# main.net
KiCad netlist of a schematic drawn in Altium Designer
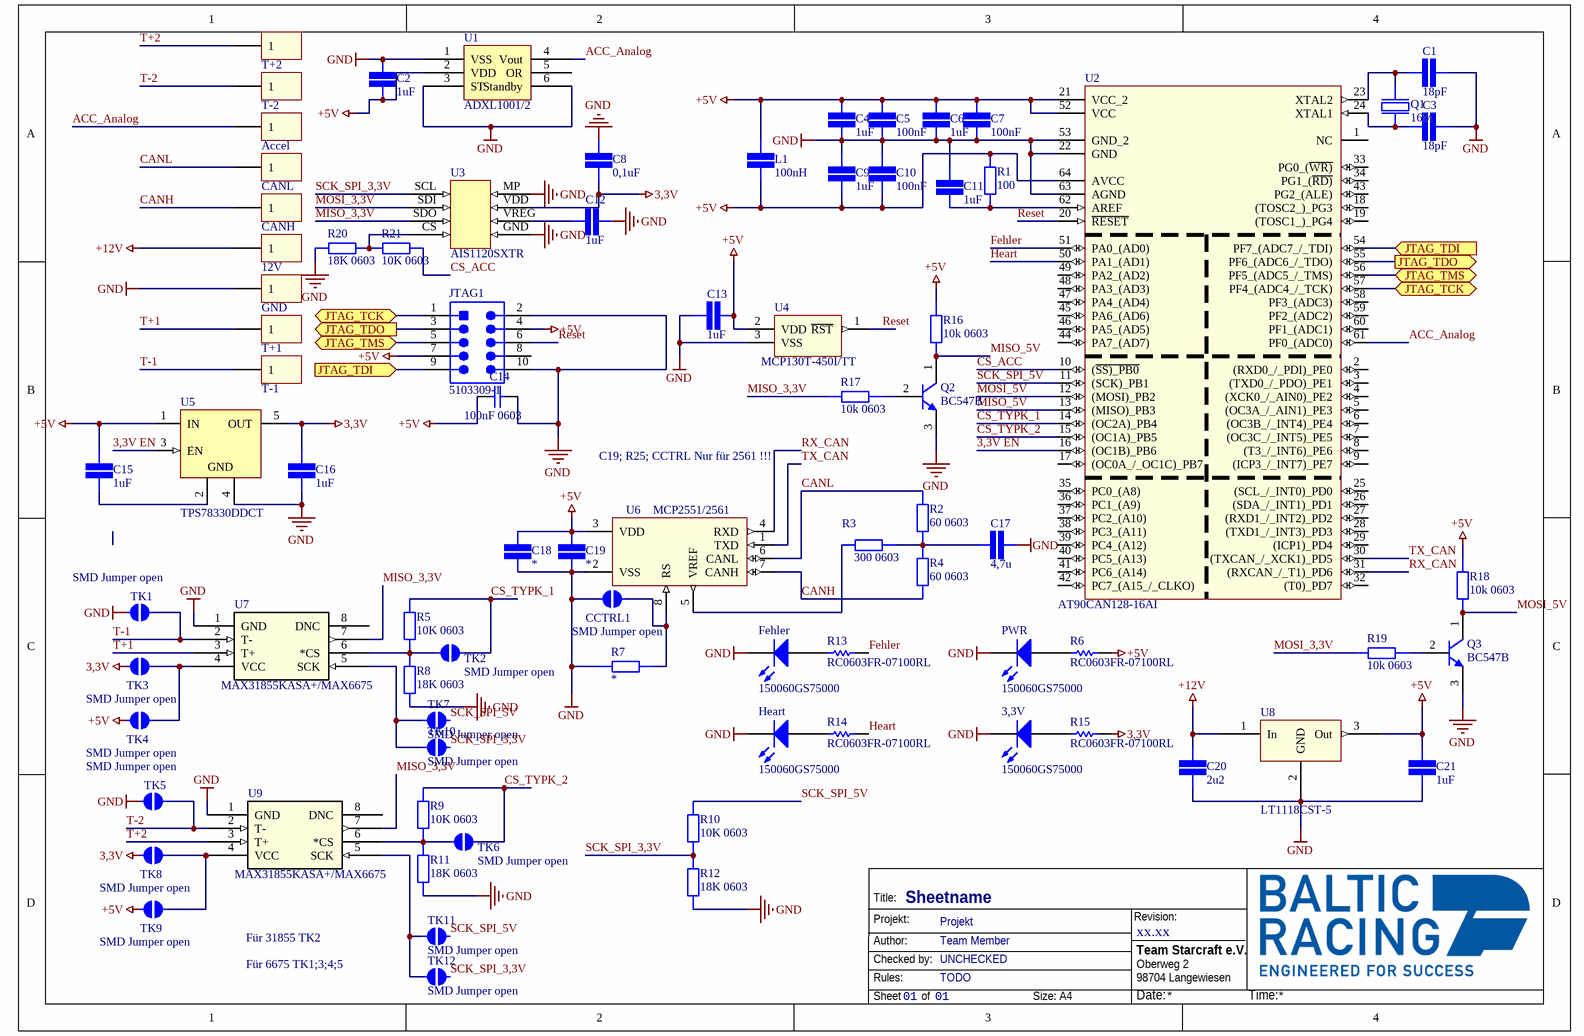
[diagram p0: main.SchDoc]

(export (version "E")
  (design (tool "Eeschema 10.0.6"))
  (components
    (comp (ref "3,3V")
      (value "150060GS75000")
      (footprint "0603_A")
      (description "SMD mono-color Chip LED, WL-SMCW, Green")
      (fields (field (name "MANUFACTURER") "Wuerth Elektronik"))
      (libsource (lib "Altium Content Vault") (part "WE-LED_K1A2-2"))
    )
    (comp (ref "12V")
      (value "61300111121")
      (footprint "61300111121")
      (description "WR-PHD 2.54 mm THT Pin Header, 1p")
      (fields (field (name "PUBLISHER") "Wurth Elektronik"))
      (libsource (lib "ALTIUM-PHD_2_54_THT_DUAL_PIN_HEADER_6130XX21121") (part "61300111121"))
    )
    (comp (ref "Accel")
      (value "61300111121")
      (footprint "61300111121")
      (description "WR-PHD 2.54 mm THT Pin Header, 1p")
      (fields (field (name "PUBLISHER") "Wurth Elektronik"))
      (libsource (lib "ALTIUM-PHD_2_54_THT_DUAL_PIN_HEADER_6130XX21121") (part "61300111121"))
    )
    (comp (ref "C1")
      (value "18pF")
      (footprint "CAP 0603/1608")
      (description "Capacitor with multiple Footprints")
      (fields (field (name "Comment") "SMD Capacitor"))
      (libsource (lib "Standardbauteile") (part "SMD Capacitor"))
    )
    (comp (ref "C2")
      (value "1uF")
      (footprint "CAP 0603/1608")
      (description "Capacitor with multiple Footprints")
      (fields (field (name "Comment") "SMD Capacitor"))
      (libsource (lib "") (part "SMD Capacitor_1"))
    )
    (comp (ref "C3")
      (value "18pF")
      (footprint "CAP 0603/1608")
      (description "Capacitor with multiple Footprints")
      (fields (field (name "Comment") "SMD Capacitor"))
      (libsource (lib "Standardbauteile") (part "SMD Capacitor"))
    )
    (comp (ref "C4")
      (value "1uF")
      (footprint "CAP 0603/1608")
      (description "Capacitor with multiple Footprints")
      (fields (field (name "Comment") "SMD Capacitor"))
      (libsource (lib "") (part "SMD Capacitor_1"))
    )
    (comp (ref "C5")
      (value "100nF")
      (footprint "CAP 0603/1608")
      (description "Capacitor with multiple Footprints")
      (fields (field (name "Comment") "SMD Capacitor"))
      (libsource (lib "") (part "SMD Capacitor_1"))
    )
    (comp (ref "C6")
      (value "1uF")
      (footprint "CAP 0603/1608")
      (description "Capacitor with multiple Footprints")
      (fields (field (name "Comment") "SMD Capacitor"))
      (libsource (lib "") (part "SMD Capacitor_1"))
    )
    (comp (ref "C7")
      (value "100nF")
      (footprint "CAP 0603/1608")
      (description "Capacitor with multiple Footprints")
      (fields (field (name "Comment") "SMD Capacitor"))
      (libsource (lib "") (part "SMD Capacitor_1"))
    )
    (comp (ref "C8")
      (value "0,1uF")
      (footprint "CAP 0603/1608")
      (description "Capacitor with multiple Footprints")
      (fields (field (name "Comment") "SMD Capacitor"))
      (libsource (lib "") (part "SMD Capacitor_1"))
    )
    (comp (ref "C9")
      (value "1uF")
      (footprint "CAP 0603/1608")
      (description "Capacitor with multiple Footprints")
      (fields (field (name "Comment") "SMD Capacitor"))
      (libsource (lib "") (part "SMD Capacitor_1"))
    )
    (comp (ref "C10")
      (value "100nF")
      (footprint "CAP 0603/1608")
      (description "Capacitor with multiple Footprints")
      (fields (field (name "Comment") "SMD Capacitor"))
      (libsource (lib "") (part "SMD Capacitor_1"))
    )
    (comp (ref "C11")
      (value "1uF")
      (footprint "CAP 0603/1608")
      (description "Capacitor with multiple Footprints")
      (fields (field (name "Comment") "SMD Capacitor"))
      (libsource (lib "") (part "SMD Capacitor_1"))
    )
    (comp (ref "C12")
      (value "1uF")
      (footprint "CAP 0603/1608")
      (description "Capacitor with multiple Footprints")
      (fields (field (name "Comment") "SMD Capacitor"))
      (libsource (lib "") (part "SMD Capacitor_2"))
    )
    (comp (ref "C13")
      (value "1uF")
      (footprint "CAP 0603/1608")
      (description "Capacitor with multiple Footprints")
      (fields (field (name "Comment") "SMD Capacitor"))
      (libsource (lib "Standardbauteile") (part "SMD Capacitor"))
    )
    (comp (ref "C14")
      (value "100nF 0603")
      (footprint "CAPC0603(1608)100_L")
      (description "CAP 100nF 10V ±5% 0603 (1608 Metric) Thickness 1mm SMD")
      (fields (field (name "TOLERANCE") "Â±5%"))
      (libsource (lib "Altium Content Vault") (part "CAP"))
    )
    (comp (ref "C15")
      (value "1uF")
      (footprint "CAP 0603/1608")
      (description "Capacitor with multiple Footprints")
      (fields (field (name "Comment") "SMD Capacitor 1uF"))
      (libsource (lib "") (part "SMD Capacitor_1"))
    )
    (comp (ref "C16")
      (value "1uF")
      (footprint "CAP 0603/1608")
      (description "Capacitor with multiple Footprints")
      (fields (field (name "Comment") "SMD Capacitor 1uF"))
      (libsource (lib "") (part "SMD Capacitor_1"))
    )
    (comp (ref "C17")
      (value "4,7u")
      (footprint "CAP 0603/1608")
      (description "Capacitor with multiple Footprints")
      (fields (field (name "Comment") "SMD Capacitor"))
      (libsource (lib "") (part "SMD Capacitor_2"))
    )
    (comp (ref "C18")
      (value "SMD Capacitor")
      (footprint "CAP 0603/1608")
      (description "Capacitor with multiple Footprints")
      (fields (field (name "ALTIUM_VALUE") "*"))
      (libsource (lib "") (part "SMD Capacitor_1"))
    )
    (comp (ref "C19")
      (value "SMD Capacitor")
      (footprint "CAP 0603/1608")
      (description "Capacitor with multiple Footprints")
      (fields (field (name "ALTIUM_VALUE") "*"))
      (libsource (lib "") (part "SMD Capacitor_1"))
    )
    (comp (ref "C20")
      (value "2u2")
      (footprint "CAP 0603/1608")
      (description "Capacitor with multiple Footprints")
      (fields (field (name "Comment") "SMD Capacitor"))
      (libsource (lib "") (part "SMD Capacitor_1"))
    )
    (comp (ref "C21")
      (value "1uF")
      (footprint "CAP 0603/1608")
      (description "Capacitor with multiple Footprints")
      (fields (field (name "Comment") "SMD Capacitor"))
      (libsource (lib "") (part "SMD Capacitor_1"))
    )
    (comp (ref "CANH")
      (value "61300111121")
      (footprint "61300111121")
      (description "WR-PHD 2.54 mm THT Pin Header, 1p")
      (fields (field (name "PUBLISHER") "Wurth Elektronik"))
      (libsource (lib "ALTIUM-PHD_2_54_THT_DUAL_PIN_HEADER_6130XX21121") (part "61300111121"))
    )
    (comp (ref "CANL")
      (value "61300111121")
      (footprint "61300111121")
      (description "WR-PHD 2.54 mm THT Pin Header, 1p")
      (fields (field (name "PUBLISHER") "Wurth Elektronik"))
      (libsource (lib "ALTIUM-PHD_2_54_THT_DUAL_PIN_HEADER_6130XX21121") (part "61300111121"))
    )
    (comp (ref "CCTRL1")
      (value "SMD Jumper open")
      (footprint "SMD-JUMPER-OPEN")
      (libsource (lib "Standardbauteile") (part "SMD Jumper open"))
    )
    (comp (ref "Fehler")
      (value "150060GS75000")
      (footprint "0603_A")
      (description "SMD mono-color Chip LED, WL-SMCW, Green")
      (fields (field (name "MANUFACTURER") "Wuerth Elektronik"))
      (libsource (lib "Altium Content Vault") (part "WE-LED_K1A2-2"))
    )
    (comp (ref "GND")
      (value "61300111121")
      (footprint "61300111121")
      (description "WR-PHD 2.54 mm THT Pin Header, 1p")
      (fields (field (name "PUBLISHER") "Wurth Elektronik"))
      (libsource (lib "ALTIUM-PHD_2_54_THT_DUAL_PIN_HEADER_6130XX21121") (part "61300111121"))
    )
    (comp (ref "Heart")
      (value "150060GS75000")
      (footprint "0603_A")
      (description "SMD mono-color Chip LED, WL-SMCW, Green")
      (fields (field (name "MANUFACTURER") "Wuerth Elektronik"))
      (libsource (lib "Altium Content Vault") (part "WE-LED_K1A2-2"))
    )
    (comp (ref "JTAG1")
      (value "5103309-1")
      (footprint "TECO-5103309-1_V")
      (fields (field (name "MANUFACTURER") "TE Connectivity"))
      (libsource (lib "Altium Content Vault") (part "CN-2P-M-R10"))
    )
    (comp (ref "L1")
      (value "100nH")
      (footprint "CAP 0603/1608")
      (description "Capacitor with multiple Footprints")
      (fields (field (name "Comment") "SMD Capacitor"))
      (libsource (lib "") (part "SMD Capacitor_1"))
    )
    (comp (ref "PWR")
      (value "150060GS75000")
      (footprint "0603_A")
      (description "SMD mono-color Chip LED, WL-SMCW, Green")
      (fields (field (name "MANUFACTURER") "Wuerth Elektronik"))
      (libsource (lib "Altium Content Vault") (part "WE-LED_K1A2-2"))
    )
    (comp (ref "Q1")
      (value "16M")
      (footprint "NDK NX5032GA")
      (description "16 MHz Quartz")
      (libsource (lib "Standardbauteile") (part "16 MHz Quartz"))
    )
    (comp (ref "Q2")
      (value "BC547B")
      (footprint "ONSC-TO-92-3-29-11")
      (description "Amplifier Transistor, NPN Silicon, 3-Pin TO-92, Bulk Box")
      (fields (field (name "MANUFACTURER") "On Semiconductor"))
      (libsource (lib "Altium Content Vault") (part "ONSC-NPN-C1B2E3-3"))
    )
    (comp (ref "Q3")
      (value "BC547B")
      (footprint "ONSC-TO-92-3-29-11")
      (description "Amplifier Transistor, NPN Silicon, 3-Pin TO-92, Bulk Box")
      (fields (field (name "MANUFACTURER") "On Semiconductor"))
      (libsource (lib "Altium Content Vault") (part "ONSC-NPN-C1B2E3-3"))
    )
    (comp (ref "R1")
      (value "100")
      (footprint "STACKPOLE CSR0603")
      (description "Resistor with multiple footprints")
      (fields (field (name "Comment") "SMD Resistor"))
      (libsource (lib "Standardbauteile") (part "SMD Resistor"))
    )
    (comp (ref "R2")
      (value "60 0603")
      (footprint "STACKPOLE CSR0603")
      (description "Resistor with multiple footprints")
      (fields (field (name "Comment") "SMD Resistor"))
      (libsource (lib "Standardbauteile") (part "SMD Resistor"))
    )
    (comp (ref "R3")
      (value "300 0603")
      (footprint "STACKPOLE CSR0603")
      (description "Resistor with multiple footprints")
      (fields (field (name "Comment") "SMD Resistor"))
      (libsource (lib "Standardbauteile") (part "SMD Resistor"))
    )
    (comp (ref "R4")
      (value "60 0603")
      (footprint "STACKPOLE CSR0603")
      (description "Resistor with multiple footprints")
      (fields (field (name "Comment") "SMD Resistor"))
      (libsource (lib "Standardbauteile") (part "SMD Resistor"))
    )
    (comp (ref "R5")
      (value "10K 0603")
      (footprint "STACKPOLE CSR0603")
      (description "Resistor with multiple footprints")
      (fields (field (name "Comment") "SMD Resistor"))
      (libsource (lib "Standardbauteile") (part "SMD Resistor"))
    )
    (comp (ref "R6")
      (value "RC0603FR-07100RL")
      (footprint "RESC1608X55X25ML10T15")
      (description "Chip Resistor, 100 Ohm, +/- 1%, 0.1 W, -55 to 155 degC, 0603 (1608 Metric), RoHS, Tape and Reel")
      (fields (field (name "TOLERANCE") "1%") (field (name "MANUFACTURER") "Yageo"))
      (libsource (lib "Altium Content Vault") (part "RES-2"))
    )
    (comp (ref "R7")
      (value "SMD Resistor")
      (footprint "STACKPOLE CSR0603")
      (description "Resistor with multiple footprints")
      (fields (field (name "ALTIUM_VALUE") "*"))
      (libsource (lib "Standardbauteile") (part "SMD Resistor"))
    )
    (comp (ref "R8")
      (value "18K 0603")
      (footprint "STACKPOLE CSR0603")
      (description "Resistor with multiple footprints")
      (fields (field (name "Comment") "SMD Resistor"))
      (libsource (lib "Standardbauteile") (part "SMD Resistor"))
    )
    (comp (ref "R9")
      (value "10K 0603")
      (footprint "STACKPOLE CSR0603")
      (description "Resistor with multiple footprints")
      (fields (field (name "Comment") "SMD Resistor"))
      (libsource (lib "Standardbauteile") (part "SMD Resistor"))
    )
    (comp (ref "R10")
      (value "10K 0603")
      (footprint "STACKPOLE CSR0603")
      (description "Resistor with multiple footprints")
      (fields (field (name "Comment") "SMD Resistor"))
      (libsource (lib "Standardbauteile") (part "SMD Resistor"))
    )
    (comp (ref "R11")
      (value "18K 0603")
      (footprint "STACKPOLE CSR0603")
      (description "Resistor with multiple footprints")
      (fields (field (name "Comment") "SMD Resistor"))
      (libsource (lib "Standardbauteile") (part "SMD Resistor"))
    )
    (comp (ref "R12")
      (value "18K 0603")
      (footprint "STACKPOLE CSR0603")
      (description "Resistor with multiple footprints")
      (fields (field (name "Comment") "SMD Resistor"))
      (libsource (lib "Standardbauteile") (part "SMD Resistor"))
    )
    (comp (ref "R13")
      (value "RC0603FR-07100RL")
      (footprint "RESC1608X55X25ML10T15")
      (description "Chip Resistor, 100 Ohm, +/- 1%, 0.1 W, -55 to 155 degC, 0603 (1608 Metric), RoHS, Tape and Reel")
      (fields (field (name "TOLERANCE") "1%") (field (name "MANUFACTURER") "Yageo"))
      (libsource (lib "Altium Content Vault") (part "RES-2"))
    )
    (comp (ref "R14")
      (value "RC0603FR-07100RL")
      (footprint "RESC1608X55X25ML10T15")
      (description "Chip Resistor, 100 Ohm, +/- 1%, 0.1 W, -55 to 155 degC, 0603 (1608 Metric), RoHS, Tape and Reel")
      (fields (field (name "TOLERANCE") "1%") (field (name "MANUFACTURER") "Yageo"))
      (libsource (lib "Altium Content Vault") (part "RES-2"))
    )
    (comp (ref "R15")
      (value "RC0603FR-07100RL")
      (footprint "RESC1608X55X25ML10T15")
      (description "Chip Resistor, 100 Ohm, +/- 1%, 0.1 W, -55 to 155 degC, 0603 (1608 Metric), RoHS, Tape and Reel")
      (fields (field (name "TOLERANCE") "1%") (field (name "MANUFACTURER") "Yageo"))
      (libsource (lib "Altium Content Vault") (part "RES-2"))
    )
    (comp (ref "R16")
      (value "10k 0603")
      (footprint "STACKPOLE CSR0603")
      (description "Resistor with multiple footprints")
      (fields (field (name "Comment") "SMD Resistor"))
      (libsource (lib "Standardbauteile") (part "SMD Resistor"))
    )
    (comp (ref "R17")
      (value "10k 0603")
      (footprint "STACKPOLE CSR0603")
      (description "Resistor with multiple footprints")
      (fields (field (name "Comment") "SMD Resistor"))
      (libsource (lib "Standardbauteile") (part "SMD Resistor"))
    )
    (comp (ref "R18")
      (value "10k 0603")
      (footprint "STACKPOLE CSR0603")
      (description "Resistor with multiple footprints")
      (fields (field (name "Comment") "SMD Resistor"))
      (libsource (lib "Standardbauteile") (part "SMD Resistor"))
    )
    (comp (ref "R19")
      (value "10k 0603")
      (footprint "STACKPOLE CSR0603")
      (description "Resistor with multiple footprints")
      (fields (field (name "Comment") "SMD Resistor"))
      (libsource (lib "Standardbauteile") (part "SMD Resistor"))
    )
    (comp (ref "R20")
      (value "18K 0603")
      (footprint "STACKPOLE CSR0603")
      (description "Resistor with multiple footprints")
      (fields (field (name "Comment") "SMD Resistor"))
      (libsource (lib "Standardbauteile") (part "SMD Resistor"))
    )
    (comp (ref "R21")
      (value "10K 0603")
      (footprint "STACKPOLE CSR0603")
      (description "Resistor with multiple footprints")
      (fields (field (name "Comment") "SMD Resistor"))
      (libsource (lib "Standardbauteile") (part "SMD Resistor"))
    )
    (comp (ref "T+1")
      (value "61300111121")
      (footprint "61300111121")
      (description "WR-PHD 2.54 mm THT Pin Header, 1p")
      (fields (field (name "PUBLISHER") "Wurth Elektronik"))
      (libsource (lib "ALTIUM-PHD_2_54_THT_DUAL_PIN_HEADER_6130XX21121") (part "61300111121"))
    )
    (comp (ref "T+2")
      (value "61300111121")
      (footprint "61300111121")
      (description "WR-PHD 2.54 mm THT Pin Header, 1p")
      (fields (field (name "PUBLISHER") "Wurth Elektronik"))
      (libsource (lib "ALTIUM-PHD_2_54_THT_DUAL_PIN_HEADER_6130XX21121") (part "61300111121"))
    )
    (comp (ref "T-1")
      (value "61300111121")
      (footprint "61300111121")
      (description "WR-PHD 2.54 mm THT Pin Header, 1p")
      (fields (field (name "PUBLISHER") "Wurth Elektronik"))
      (libsource (lib "ALTIUM-PHD_2_54_THT_DUAL_PIN_HEADER_6130XX21121") (part "61300111121"))
    )
    (comp (ref "T-2")
      (value "61300111121")
      (footprint "61300111121")
      (description "WR-PHD 2.54 mm THT Pin Header, 1p")
      (fields (field (name "PUBLISHER") "Wurth Elektronik"))
      (libsource (lib "ALTIUM-PHD_2_54_THT_DUAL_PIN_HEADER_6130XX21121") (part "61300111121"))
    )
    (comp (ref "TK1")
      (value "SMD Jumper open")
      (footprint "SMD-JUMPER-OPEN")
      (libsource (lib "Standardbauteile") (part "SMD Jumper open"))
    )
    (comp (ref "TK2")
      (value "SMD Jumper open")
      (footprint "SMD-JUMPER-OPEN")
      (libsource (lib "Standardbauteile") (part "SMD Jumper open"))
    )
    (comp (ref "TK3")
      (value "SMD Jumper open")
      (footprint "SMD-JUMPER-OPEN")
      (libsource (lib "Standardbauteile") (part "SMD Jumper open"))
    )
    (comp (ref "TK4")
      (value "SMD Jumper open")
      (footprint "SMD-JUMPER-OPEN")
      (libsource (lib "Standardbauteile") (part "SMD Jumper open"))
    )
    (comp (ref "TK5")
      (value "SMD Jumper open")
      (footprint "SMD-JUMPER-OPEN")
      (libsource (lib "Standardbauteile") (part "SMD Jumper open"))
    )
    (comp (ref "TK6")
      (value "SMD Jumper open")
      (footprint "SMD-JUMPER-OPEN")
      (libsource (lib "Standardbauteile") (part "SMD Jumper open"))
    )
    (comp (ref "TK7")
      (value "SMD Jumper open")
      (footprint "SMD-JUMPER-OPEN")
      (libsource (lib "Standardbauteile") (part "SMD Jumper open"))
    )
    (comp (ref "TK8")
      (value "SMD Jumper open")
      (footprint "SMD-JUMPER-OPEN")
      (libsource (lib "Standardbauteile") (part "SMD Jumper open"))
    )
    (comp (ref "TK9")
      (value "SMD Jumper open")
      (footprint "SMD-JUMPER-OPEN")
      (libsource (lib "Standardbauteile") (part "SMD Jumper open"))
    )
    (comp (ref "TK10")
      (value "SMD Jumper open")
      (footprint "SMD-JUMPER-OPEN")
      (libsource (lib "Standardbauteile") (part "SMD Jumper open"))
    )
    (comp (ref "TK11")
      (value "SMD Jumper open")
      (footprint "SMD-JUMPER-OPEN")
      (libsource (lib "Standardbauteile") (part "SMD Jumper open"))
    )
    (comp (ref "TK12")
      (value "SMD Jumper open")
      (footprint "SMD-JUMPER-OPEN")
      (libsource (lib "Standardbauteile") (part "SMD Jumper open"))
    )
    (comp (ref "U1")
      (value "ADXL1001/2")
      (footprint "PCBComponent_1")
      (libsource (lib "Eric") (part "ADXL1001/2"))
    )
    (comp (ref "U2")
      (value "AT90CAN128-16AI")
      (footprint "*QFP80P1600X1600X120-64N")
      (description "Ic Mcu 8bit 128kb Flash 64tqfp")
      (fields (field (name "MF") "Microchip"))
      (libsource (lib "Eric") (part "AT90CAN128-16AI"))
    )
    (comp (ref "U3")
      (value "AIS1120SXTR")
      (footprint "SOIC8; SOIC127P600X175-8N")
      (libsource (lib "Integrated_LibraryLukas") (part "AIS1120SXTR"))
    )
    (comp (ref "U4")
      (value "MCP130T-450I/TT")
      (footprint "*SOT95P237X112-3N")
      (description "System Supervisors - Power Supply Monitors with Reset Generators Open Drain Low")
      (fields (field (name "MF") "Microchip") (field (name "MP") "MCP120T-450I/TT"))
      (libsource (lib "Eric") (part "MCP130T-450I/TT"))
    )
    (comp (ref "U5")
      (value "TPS78330DDCT")
      (footprint "DDC0005A_L")
      (fields (field (name "MANUFACTURER") "Texas Instruments"))
      (libsource (lib "Altium Content Vault") (part "TI-TPS78XXX-DDC5"))
    )
    (comp (ref "U6")
      (value "MCP2551/2561")
      (footprint "*SOIC127P600X175-8N")
      (description "MCP2551 Series 5.5 V 1 Mb/s Surface Mount High-Speed CAN Transceiver - SOIC-8")
      (fields (field (name "MP") "MCP2551-I/SN") (field (name "MF") "Microchip"))
      (libsource (lib "Eric") (part "MCP2551-I/SN"))
    )
    (comp (ref "U7")
      (value "MAX31855KASA+/MAX6675")
      (footprint "SOIC8")
      (description "No Description Available")
      (fields
        (field (name "MANUFACTURER_PART_NUMBER") "MAX31855KASA+")
        (field (name "COPYRIGHT") "Copyright (C) 2018 Accelerated Designs. All rights reserved")
      )
      (libsource (lib "Eric") (part "MAX31855KASA+"))
    )
    (comp (ref "U8")
      (value "LT1118CST-5")
      (footprint "*SOT230P700X180-4N")
      (description "or UA78M if used topdown (in and out changed)")
      (libsource (lib "Eric") (part "LT1118CST-5"))
    )
    (comp (ref "U9")
      (value "MAX31855KASA+/MAX6675")
      (footprint "SOIC8")
      (description "No Description Available")
      (fields
        (field (name "MANUFACTURER_PART_NUMBER") "MAX31855KASA+")
        (field (name "COPYRIGHT") "Copyright (C) 2018 Accelerated Designs. All rights reserved")
      )
      (libsource (lib "Eric") (part "MAX31855KASA+"))
    )
  )
  (nets
    (net (code "1") (name "+5V") (class "Default")
      (node (ref "C10") (pin "1") (pinfunction "1_1") (pintype "passive"))
      (node (ref "C13") (pin "1") (pinfunction "1_1") (pintype "passive"))
      (node (ref "C14") (pin "1") (pinfunction "1_1") (pintype "passive"))
      (node (ref "C15") (pin "2") (pinfunction "2_2") (pintype "passive"))
      (node (ref "C18") (pin "2") (pinfunction "2_2") (pintype "passive"))
      (node (ref "C19") (pin "2") (pinfunction "2_2") (pintype "passive"))
      (node (ref "C2") (pin "1") (pinfunction "1_1") (pintype "passive"))
      (node (ref "C21") (pin "2") (pinfunction "2_2") (pintype "passive"))
      (node (ref "C4") (pin "2") (pinfunction "2_2") (pintype "passive"))
      (node (ref "C5") (pin "2") (pinfunction "2_2") (pintype "passive"))
      (node (ref "C6") (pin "2") (pinfunction "2_2") (pintype "passive"))
      (node (ref "C7") (pin "2") (pinfunction "2_2") (pintype "passive"))
      (node (ref "C9") (pin "1") (pinfunction "1_1") (pintype "passive"))
      (node (ref "JTAG1") (pin "4") (pinfunction "4_4") (pintype "passive"))
      (node (ref "JTAG1") (pin "7") (pinfunction "7_7") (pintype "passive"))
      (node (ref "L1") (pin "1") (pinfunction "1_1") (pintype "passive"))
      (node (ref "L1") (pin "2") (pinfunction "2_2") (pintype "passive"))
      (node (ref "R1") (pin "2") (pinfunction "2_2") (pintype "passive"))
      (node (ref "R16") (pin "1") (pinfunction "1_1") (pintype "passive"))
      (node (ref "R18") (pin "1") (pinfunction "1_1") (pintype "passive"))
      (node (ref "R6") (pin "1") (pinfunction "1_1") (pintype "passive"))
      (node (ref "TK4") (pin "1") (pinfunction "1_1") (pintype "passive"))
      (node (ref "TK9") (pin "1") (pinfunction "1_1") (pintype "passive"))
      (node (ref "U1") (pin "2") (pinfunction "VDD_2") (pintype "passive"))
      (node (ref "U2") (pin "21") (pinfunction "VCC_2_21") (pintype "power_in"))
      (node (ref "U2") (pin "52") (pinfunction "VCC_52") (pintype "power_in"))
      (node (ref "U2") (pin "64") (pinfunction "AVCC_64") (pintype "power_in"))
      (node (ref "U4") (pin "2") (pinfunction "VDD_2") (pintype "power_in"))
      (node (ref "U5") (pin "1") (pinfunction "IN_1") (pintype "power_in"))
      (node (ref "U6") (pin "3") (pinfunction "VDD_3") (pintype "power_in"))
      (node (ref "U8") (pin "3") (pinfunction "Out_3") (pintype "output"))
    )
    (net (code "2") (name "+12V") (class "Default")
      (node (ref "12V") (pin "1") (pinfunction "1_1") (pintype "passive"))
      (node (ref "C20") (pin "2") (pinfunction "2_2") (pintype "passive"))
      (node (ref "U8") (pin "1") (pinfunction "In_1") (pintype "power_in"))
    )
    (net (code "3") (name "/3,3V EN") (class "Default")
      (node (ref "U2") (pin "16") (pinfunction "(OC1B)_PB6_16") (pintype "bidirectional"))
      (node (ref "U5") (pin "3") (pinfunction "EN_3") (pintype "input"))
    )
    (net (code "4") (name "/ACC_Analog") (class "Default")
      (node (ref "Accel") (pin "1") (pinfunction "1_1") (pintype "passive"))
      (node (ref "U1") (pin "4") (pinfunction "Vout_4") (pintype "passive"))
      (node (ref "U2") (pin "61") (pinfunction "PF0_(ADC0)_61") (pintype "bidirectional"))
    )
    (net (code "5") (name "/CANH") (class "Default")
      (node (ref "CANH") (pin "1") (pinfunction "1_1") (pintype "passive"))
      (node (ref "R4") (pin "2") (pinfunction "2_2") (pintype "passive"))
      (node (ref "U6") (pin "7") (pinfunction "CANH_7") (pintype "bidirectional"))
    )
    (net (code "6") (name "/CANL") (class "Default")
      (node (ref "CANL") (pin "1") (pinfunction "1_1") (pintype "passive"))
      (node (ref "R2") (pin "1") (pinfunction "1_1") (pintype "passive"))
      (node (ref "U6") (pin "6") (pinfunction "CANL_6") (pintype "bidirectional"))
    )
    (net (code "7") (name "/CS_ACC") (class "Default")
      (node (ref "R21") (pin "2") (pinfunction "2_2") (pintype "passive"))
      (node (ref "U2") (pin "10") (pinfunction "(~{SS)_PB0}_10") (pintype "bidirectional"))
    )
    (net (code "8") (name "/CS_TYPK_1") (class "Default")
      (node (ref "R5") (pin "2") (pinfunction "2_2") (pintype "passive"))
      (node (ref "TK2") (pin "2") (pinfunction "2_2") (pintype "passive"))
      (node (ref "U2") (pin "14") (pinfunction "(OC2A)_PB4_14") (pintype "bidirectional"))
    )
    (net (code "9") (name "/CS_TYPK_2") (class "Default")
      (node (ref "R9") (pin "2") (pinfunction "2_2") (pintype "passive"))
      (node (ref "TK6") (pin "2") (pinfunction "2_2") (pintype "passive"))
      (node (ref "U2") (pin "15") (pinfunction "(OC1A)_PB5_15") (pintype "bidirectional"))
    )
    (net (code "10") (name "/Fehler") (class "Default")
      (node (ref "R13") (pin "1") (pinfunction "1_1") (pintype "passive"))
      (node (ref "U2") (pin "51") (pinfunction "PA0_(AD0)_51") (pintype "bidirectional"))
    )
    (net (code "11") (name "/Heart") (class "Default")
      (node (ref "R14") (pin "1") (pinfunction "1_1") (pintype "passive"))
      (node (ref "U2") (pin "50") (pinfunction "PA1_(AD1)_50") (pintype "bidirectional"))
    )
    (net (code "12") (name "/JTAG_TCK") (class "Default")
      (node (ref "JTAG1") (pin "1") (pinfunction "1_1") (pintype "passive"))
      (node (ref "U2") (pin "57") (pinfunction "PF4_(ADC4_/_TCK)_57") (pintype "bidirectional"))
    )
    (net (code "13") (name "/JTAG_TDI") (class "Default")
      (node (ref "JTAG1") (pin "9") (pinfunction "9_9") (pintype "passive"))
      (node (ref "U2") (pin "54") (pinfunction "PF7_(ADC7_/_TDI)_54") (pintype "bidirectional"))
    )
    (net (code "14") (name "/JTAG_TDO") (class "Default")
      (node (ref "JTAG1") (pin "3") (pinfunction "3_3") (pintype "passive"))
      (node (ref "U2") (pin "55") (pinfunction "PF6_(ADC6_/_TDO)_55") (pintype "bidirectional"))
    )
    (net (code "15") (name "/JTAG_TMS") (class "Default")
      (node (ref "JTAG1") (pin "5") (pinfunction "5_5") (pintype "passive"))
      (node (ref "U2") (pin "56") (pinfunction "PF5_(ADC5_/_TMS)_56") (pintype "bidirectional"))
    )
    (net (code "16") (name "/MISO_3,3V") (class "Default")
      (node (ref "R17") (pin "1") (pinfunction "1_1") (pintype "passive"))
      (node (ref "U3") (pin "SDO") (pintype "input"))
      (node (ref "U7") (pin "7") (pinfunction "SO_7") (pintype "output"))
      (node (ref "U9") (pin "7") (pinfunction "SO_7") (pintype "output"))
    )
    (net (code "17") (name "/MISO_5V") (class "Default")
      (node (ref "Q2") (pin "1") (pinfunction "C_1") (pintype "passive"))
      (node (ref "R16") (pin "2") (pinfunction "2_2") (pintype "passive"))
      (node (ref "U2") (pin "13") (pinfunction "(MISO)_PB3_13") (pintype "bidirectional"))
    )
    (net (code "18") (name "/MOSI_3,3V") (class "Default")
      (node (ref "R19") (pin "1") (pinfunction "1_1") (pintype "passive"))
      (node (ref "U3") (pin "SDI") (pintype "input"))
    )
    (net (code "19") (name "/MOSI_5V") (class "Default")
      (node (ref "Q3") (pin "1") (pinfunction "C_1") (pintype "passive"))
      (node (ref "R18") (pin "2") (pinfunction "2_2") (pintype "passive"))
      (node (ref "U2") (pin "12") (pinfunction "(MOSI)_PB2_12") (pintype "bidirectional"))
    )
    (net (code "20") (name "/RX_CAN") (class "Default")
      (node (ref "U2") (pin "31") (pinfunction "(RXCAN_/_T1)_PD6_31") (pintype "bidirectional"))
      (node (ref "U6") (pin "4") (pinfunction "RXD_4") (pintype "output"))
    )
    (net (code "21") (name "/Reset") (class "Default")
      (node (ref "JTAG1") (pin "6") (pinfunction "6_6") (pintype "passive"))
      (node (ref "U2") (pin "20") (pinfunction "~{RESET}_20") (pintype "input"))
      (node (ref "U4") (pin "1") (pinfunction "~{RST}_1") (pintype "output"))
    )
    (net (code "22") (name "/SCK_SPI_3,3V") (class "Default")
      (node (ref "R10") (pin "1") (pinfunction "1_1") (pintype "passive"))
      (node (ref "R12") (pin "2") (pinfunction "2_2") (pintype "passive"))
      (node (ref "TK10") (pin "1") (pinfunction "1_1") (pintype "passive"))
      (node (ref "TK12") (pin "1") (pinfunction "1_1") (pintype "passive"))
      (node (ref "U3") (pin "SCL") (pintype "input"))
    )
    (net (code "23") (name "/SCK_SPI_5V") (class "Default")
      (node (ref "R10") (pin "2") (pinfunction "2_2") (pintype "passive"))
      (node (ref "TK11") (pin "1") (pinfunction "1_1") (pintype "passive"))
      (node (ref "TK7") (pin "1") (pinfunction "1_1") (pintype "passive"))
      (node (ref "U2") (pin "11") (pinfunction "(SCK)_PB1_11") (pintype "bidirectional"))
    )
    (net (code "24") (name "/T+1") (class "Default")
      (node (ref "T+1") (pin "1") (pinfunction "1_1") (pintype "passive"))
      (node (ref "U7") (pin "3") (pinfunction "T+_3") (pintype "input"))
    )
    (net (code "25") (name "/T+2") (class "Default")
      (node (ref "T+2") (pin "1") (pinfunction "1_1") (pintype "passive"))
      (node (ref "U9") (pin "3") (pinfunction "T+_3") (pintype "input"))
    )
    (net (code "26") (name "/T-1") (class "Default")
      (node (ref "T-1") (pin "1") (pinfunction "1_1") (pintype "passive"))
      (node (ref "TK1") (pin "2") (pinfunction "2_2") (pintype "passive"))
      (node (ref "U7") (pin "2") (pinfunction "T-_2") (pintype "input"))
    )
    (net (code "27") (name "/T-2") (class "Default")
      (node (ref "T-2") (pin "1") (pinfunction "1_1") (pintype "passive"))
      (node (ref "TK5") (pin "2") (pinfunction "2_2") (pintype "passive"))
      (node (ref "U9") (pin "2") (pinfunction "T-_2") (pintype "input"))
    )
    (net (code "28") (name "/TX_CAN") (class "Default")
      (node (ref "U2") (pin "30") (pinfunction "(TXCAN_/_XCK1)_PD5_30") (pintype "bidirectional"))
      (node (ref "U6") (pin "1") (pinfunction "TXD_1") (pintype "input"))
    )
    (net (code "29") (name "3,3V") (class "Default")
      (node (ref "C16") (pin "2") (pinfunction "2_2") (pintype "passive"))
      (node (ref "C8") (pin "1") (pinfunction "1_1") (pintype "passive"))
      (node (ref "R15") (pin "1") (pinfunction "1_1") (pintype "passive"))
      (node (ref "TK3") (pin "1") (pinfunction "1_1") (pintype "passive"))
      (node (ref "TK8") (pin "1") (pinfunction "1_1") (pintype "passive"))
      (node (ref "U3") (pin "VDD") (pintype "input"))
      (node (ref "U5") (pin "5") (pinfunction "OUT_5") (pintype "power_in"))
    )
    (net (code "30") (name "GND") (class "Default")
      (node (ref "3,3V") (pin "1") (pinfunction "K_1") (pintype "passive"))
      (node (ref "C1") (pin "1") (pinfunction "1_1") (pintype "passive"))
      (node (ref "C10") (pin "2") (pinfunction "2_2") (pintype "passive"))
      (node (ref "C11") (pin "2") (pinfunction "2_2") (pintype "passive"))
      (node (ref "C12") (pin "2") (pinfunction "2_2") (pintype "passive"))
      (node (ref "C13") (pin "2") (pinfunction "2_2") (pintype "passive"))
      (node (ref "C14") (pin "2") (pinfunction "2_2") (pintype "passive"))
      (node (ref "C16") (pin "1") (pinfunction "1_1") (pintype "passive"))
      (node (ref "C17") (pin "2") (pinfunction "2_2") (pintype "passive"))
      (node (ref "C18") (pin "1") (pinfunction "1_1") (pintype "passive"))
      (node (ref "C19") (pin "1") (pinfunction "1_1") (pintype "passive"))
      (node (ref "C2") (pin "2") (pinfunction "2_2") (pintype "passive"))
      (node (ref "C20") (pin "1") (pinfunction "1_1") (pintype "passive"))
      (node (ref "C21") (pin "1") (pinfunction "1_1") (pintype "passive"))
      (node (ref "C3") (pin "1") (pinfunction "1_1") (pintype "passive"))
      (node (ref "C4") (pin "1") (pinfunction "1_1") (pintype "passive"))
      (node (ref "C5") (pin "1") (pinfunction "1_1") (pintype "passive"))
      (node (ref "C6") (pin "1") (pinfunction "1_1") (pintype "passive"))
      (node (ref "C7") (pin "1") (pinfunction "1_1") (pintype "passive"))
      (node (ref "C8") (pin "2") (pinfunction "2_2") (pintype "passive"))
      (node (ref "C9") (pin "2") (pinfunction "2_2") (pintype "passive"))
      (node (ref "CCTRL1") (pin "1") (pinfunction "1_1") (pintype "passive"))
      (node (ref "Fehler") (pin "1") (pinfunction "K_1") (pintype "passive"))
      (node (ref "GND") (pin "1") (pinfunction "1_1") (pintype "passive"))
      (node (ref "Heart") (pin "1") (pinfunction "K_1") (pintype "passive"))
      (node (ref "JTAG1") (pin "10") (pinfunction "10_10") (pintype "passive"))
      (node (ref "JTAG1") (pin "2") (pinfunction "2_2") (pintype "passive"))
      (node (ref "PWR") (pin "1") (pinfunction "K_1") (pintype "passive"))
      (node (ref "Q2") (pin "3") (pinfunction "E_3") (pintype "passive"))
      (node (ref "Q3") (pin "3") (pinfunction "E_3") (pintype "passive"))
      (node (ref "R11") (pin "1") (pinfunction "1_1") (pintype "passive"))
      (node (ref "R12") (pin "1") (pinfunction "1_1") (pintype "passive"))
      (node (ref "R20") (pin "1") (pinfunction "1_1") (pintype "passive"))
      (node (ref "R7") (pin "1") (pinfunction "1_1") (pintype "passive"))
      (node (ref "R8") (pin "1") (pinfunction "1_1") (pintype "passive"))
      (node (ref "TK1") (pin "1") (pinfunction "1_1") (pintype "passive"))
      (node (ref "TK5") (pin "1") (pinfunction "1_1") (pintype "passive"))
      (node (ref "U1") (pin "1") (pinfunction "VSS_1") (pintype "passive"))
      (node (ref "U1") (pin "3") (pinfunction "ST_3") (pintype "passive"))
      (node (ref "U1") (pin "6") (pinfunction "Standby_6") (pintype "passive"))
      (node (ref "U2") (pin "22") (pinfunction "GND_22") (pintype "passive"))
      (node (ref "U2") (pin "53") (pinfunction "GND_2_53") (pintype "passive"))
      (node (ref "U2") (pin "63") (pinfunction "AGND_63") (pintype "passive"))
      (node (ref "U3") (pin "GND") (pintype "input"))
      (node (ref "U3") (pin "MP") (pintype "input"))
      (node (ref "U4") (pin "3") (pinfunction "VSS_3") (pintype "power_in"))
      (node (ref "U5") (pin "4") (pinfunction "GND_4") (pintype "power_in"))
      (node (ref "U6") (pin "2") (pinfunction "VSS_2") (pintype "passive"))
      (node (ref "U7") (pin "1") (pinfunction "GND_1") (pintype "power_in"))
      (node (ref "U8") (pin "2") (pinfunction "GND_2") (pintype "passive"))
      (node (ref "U9") (pin "1") (pinfunction "GND_1") (pintype "power_in"))
    )
    (net (code "31") (name "Net-(3,3V-A)") (class "Default")
      (node (ref "3,3V") (pin "2") (pinfunction "A_2") (pintype "passive"))
      (node (ref "R15") (pin "2") (pinfunction "2_2") (pintype "passive"))
    )
    (net (code "32") (name "Net-(C12-Pad1)") (class "Default")
      (node (ref "C12") (pin "1") (pinfunction "1_1") (pintype "passive"))
      (node (ref "U3") (pin "VREG") (pintype "input"))
    )
    (net (code "33") (name "Net-(C15-Pad1)") (class "Default")
      (node (ref "C15") (pin "1") (pinfunction "1_1") (pintype "passive"))
      (node (ref "U5") (pin "2") (pinfunction "GND_2") (pintype "power_in"))
    )
    (net (code "34") (name "Net-(C17-Pad1)") (class "Default")
      (node (ref "C17") (pin "1") (pinfunction "1_1") (pintype "passive"))
      (node (ref "R2") (pin "2") (pinfunction "2_2") (pintype "passive"))
      (node (ref "R3") (pin "2") (pinfunction "2_2") (pintype "passive"))
      (node (ref "R4") (pin "1") (pinfunction "1_1") (pintype "passive"))
    )
    (net (code "35") (name "Net-(Fehler-A)") (class "Default")
      (node (ref "Fehler") (pin "2") (pinfunction "A_2") (pintype "passive"))
      (node (ref "R13") (pin "2") (pinfunction "2_2") (pintype "passive"))
    )
    (net (code "36") (name "Net-(Heart-A)") (class "Default")
      (node (ref "Heart") (pin "2") (pinfunction "A_2") (pintype "passive"))
      (node (ref "R14") (pin "2") (pinfunction "2_2") (pintype "passive"))
    )
    (net (code "37") (name "Net-(PWR-A)") (class "Default")
      (node (ref "PWR") (pin "2") (pinfunction "A_2") (pintype "passive"))
      (node (ref "R6") (pin "2") (pinfunction "2_2") (pintype "passive"))
    )
    (net (code "38") (name "Net-(Q2-B)") (class "Default")
      (node (ref "Q2") (pin "2") (pinfunction "B_2") (pintype "passive"))
      (node (ref "R17") (pin "2") (pinfunction "2_2") (pintype "passive"))
    )
    (net (code "39") (name "Net-(Q3-B)") (class "Default")
      (node (ref "Q3") (pin "2") (pinfunction "B_2") (pintype "passive"))
      (node (ref "R19") (pin "2") (pinfunction "2_2") (pintype "passive"))
    )
    (net (code "40") (name "Net-(R20-Pad2)") (class "Default")
      (node (ref "R20") (pin "2") (pinfunction "2_2") (pintype "passive"))
      (node (ref "R21") (pin "1") (pinfunction "1_1") (pintype "passive"))
      (node (ref "U3") (pin "CS") (pintype "input"))
    )
    (net (code "41") (name "Net-(U2-AREF)") (class "Default")
      (node (ref "C11") (pin "1") (pinfunction "1_1") (pintype "passive"))
      (node (ref "R1") (pin "1") (pinfunction "1_1") (pintype "passive"))
      (node (ref "U2") (pin "62") (pinfunction "AREF_62") (pintype "input"))
    )
    (net (code "42") (name "Net-(U2-XTAL1)") (class "Default")
      (node (ref "C3") (pin "2") (pinfunction "2_2") (pintype "passive"))
      (node (ref "Q1") (pin "1") (pinfunction "1_1") (pintype "passive"))
      (node (ref "U2") (pin "24") (pinfunction "XTAL1_24") (pintype "input"))
    )
    (net (code "43") (name "Net-(U2-XTAL2)") (class "Default")
      (node (ref "C1") (pin "2") (pinfunction "2_2") (pintype "passive"))
      (node (ref "Q1") (pin "2") (pinfunction "2_2") (pintype "passive"))
      (node (ref "U2") (pin "23") (pinfunction "XTAL2_23") (pintype "output"))
    )
    (net (code "44") (name "Net-(U6-RS)") (class "Default")
      (node (ref "CCTRL1") (pin "2") (pinfunction "2_2") (pintype "passive"))
      (node (ref "R7") (pin "2") (pinfunction "2_2") (pintype "passive"))
      (node (ref "U6") (pin "8") (pinfunction "RS_8") (pintype "input"))
    )
    (net (code "45") (name "Net-(U6-VREF)") (class "Default")
      (node (ref "R3") (pin "1") (pinfunction "1_1") (pintype "passive"))
      (node (ref "U6") (pin "5") (pinfunction "VREF_5") (pintype "output"))
    )
    (net (code "46") (name "Net-(U7-*CS)") (class "Default")
      (node (ref "R5") (pin "1") (pinfunction "1_1") (pintype "passive"))
      (node (ref "R8") (pin "2") (pinfunction "2_2") (pintype "passive"))
      (node (ref "TK2") (pin "1") (pinfunction "1_1") (pintype "passive"))
      (node (ref "U7") (pin "6") (pinfunction "*CS_6") (pintype "passive"))
    )
    (net (code "47") (name "Net-(U7-SCK)") (class "Default")
      (node (ref "TK10") (pin "2") (pinfunction "2_2") (pintype "passive"))
      (node (ref "TK7") (pin "2") (pinfunction "2_2") (pintype "passive"))
      (node (ref "U7") (pin "5") (pinfunction "SCK_5") (pintype "input"))
    )
    (net (code "48") (name "Net-(U7-VCC)") (class "Default")
      (node (ref "TK3") (pin "2") (pinfunction "2_2") (pintype "passive"))
      (node (ref "TK4") (pin "2") (pinfunction "2_2") (pintype "passive"))
      (node (ref "U7") (pin "4") (pinfunction "VCC_4") (pintype "power_in"))
    )
    (net (code "49") (name "Net-(U9-*CS)") (class "Default")
      (node (ref "R11") (pin "2") (pinfunction "2_2") (pintype "passive"))
      (node (ref "R9") (pin "1") (pinfunction "1_1") (pintype "passive"))
      (node (ref "TK6") (pin "1") (pinfunction "1_1") (pintype "passive"))
      (node (ref "U9") (pin "6") (pinfunction "*CS_6") (pintype "passive"))
    )
    (net (code "50") (name "Net-(U9-SCK)") (class "Default")
      (node (ref "TK11") (pin "2") (pinfunction "2_2") (pintype "passive"))
      (node (ref "TK12") (pin "2") (pinfunction "2_2") (pintype "passive"))
      (node (ref "U9") (pin "5") (pinfunction "SCK_5") (pintype "input"))
    )
    (net (code "51") (name "Net-(U9-VCC)") (class "Default")
      (node (ref "TK8") (pin "2") (pinfunction "2_2") (pintype "passive"))
      (node (ref "TK9") (pin "2") (pinfunction "2_2") (pintype "passive"))
      (node (ref "U9") (pin "4") (pinfunction "VCC_4") (pintype "power_in"))
    )
    (net (code "52") (name "unconnected-(JTAG1-Pad8)") (class "Default")
      (node (ref "JTAG1") (pin "8") (pinfunction "8_8") (pintype "passive"))
    )
    (net (code "53") (name "unconnected-(U1-OR-Pad5)") (class "Default")
      (node (ref "U1") (pin "5") (pinfunction "OR_5") (pintype "passive"))
    )
    (net (code "54") (name "unconnected-(U2-(ICP1)_PD4-Pad29)") (class "Default")
      (node (ref "U2") (pin "29") (pinfunction "(ICP1)_PD4_29") (pintype "bidirectional"))
    )
    (net (code "55") (name "unconnected-(U2-(ICP3_{slash}_INT7)_PE7-Pad9)") (class "Default")
      (node (ref "U2") (pin "9") (pinfunction "(ICP3_/_INT7)_PE7_9") (pintype "bidirectional"))
    )
    (net (code "56") (name "unconnected-(U2-(OC0A_{slash}_OC1C)_PB7-Pad17)") (class "Default")
      (node (ref "U2") (pin "17") (pinfunction "(OC0A_/_OC1C)_PB7_17") (pintype "bidirectional"))
    )
    (net (code "57") (name "unconnected-(U2-(OC3A_{slash}_AIN1)_PE3-Pad5)") (class "Default")
      (node (ref "U2") (pin "5") (pinfunction "(OC3A_/_AIN1)_PE3_5") (pintype "bidirectional"))
    )
    (net (code "58") (name "unconnected-(U2-(OC3B_{slash}_INT4)_PE4-Pad6)") (class "Default")
      (node (ref "U2") (pin "6") (pinfunction "(OC3B_/_INT4)_PE4_6") (pintype "bidirectional"))
    )
    (net (code "59") (name "unconnected-(U2-(OC3C_{slash}_INT5)_PE5-Pad7)") (class "Default")
      (node (ref "U2") (pin "7") (pinfunction "(OC3C_/_INT5)_PE5_7") (pintype "bidirectional"))
    )
    (net (code "60") (name "unconnected-(U2-(RXD0_{slash}_PDI)_PE0-Pad2)") (class "Default")
      (node (ref "U2") (pin "2") (pinfunction "(RXD0_/_PDI)_PE0_2") (pintype "bidirectional"))
    )
    (net (code "61") (name "unconnected-(U2-(RXD1_{slash}_INT2)_PD2-Pad27)") (class "Default")
      (node (ref "U2") (pin "27") (pinfunction "(RXD1_/_INT2)_PD2_27") (pintype "bidirectional"))
    )
    (net (code "62") (name "unconnected-(U2-(SCL_{slash}_INT0)_PD0-Pad25)") (class "Default")
      (node (ref "U2") (pin "25") (pinfunction "(SCL_/_INT0)_PD0_25") (pintype "bidirectional"))
    )
    (net (code "63") (name "unconnected-(U2-(SDA_{slash}_INT1)_PD1-Pad26)") (class "Default")
      (node (ref "U2") (pin "26") (pinfunction "(SDA_/_INT1)_PD1_26") (pintype "bidirectional"))
    )
    (net (code "64") (name "unconnected-(U2-(T0)_PD7-Pad32)") (class "Default")
      (node (ref "U2") (pin "32") (pinfunction "(T0)_PD7_32") (pintype "bidirectional"))
    )
    (net (code "65") (name "unconnected-(U2-(T3_{slash}_INT6)_PE6-Pad8)") (class "Default")
      (node (ref "U2") (pin "8") (pinfunction "(T3_/_INT6)_PE6_8") (pintype "bidirectional"))
    )
    (net (code "66") (name "unconnected-(U2-(TOSC1_)_PG4-Pad19)") (class "Default")
      (node (ref "U2") (pin "19") (pinfunction "(TOSC1_)_PG4_19") (pintype "bidirectional"))
    )
    (net (code "67") (name "unconnected-(U2-(TOSC2_)_PG3-Pad18)") (class "Default")
      (node (ref "U2") (pin "18") (pinfunction "(TOSC2_)_PG3_18") (pintype "bidirectional"))
    )
    (net (code "68") (name "unconnected-(U2-(TXD0_{slash}_PDO)_PE1-Pad3)") (class "Default")
      (node (ref "U2") (pin "3") (pinfunction "(TXD0_/_PDO)_PE1_3") (pintype "bidirectional"))
    )
    (net (code "69") (name "unconnected-(U2-(TXD1_{slash}_INT3)_PD3-Pad28)") (class "Default")
      (node (ref "U2") (pin "28") (pinfunction "(TXD1_/_INT3)_PD3_28") (pintype "bidirectional"))
    )
    (net (code "70") (name "unconnected-(U2-(XCK0_{slash}_AIN0)_PE2-Pad4)") (class "Default")
      (node (ref "U2") (pin "4") (pinfunction "(XCK0_/_AIN0)_PE2_4") (pintype "bidirectional"))
    )
    (net (code "71") (name "unconnected-(U2-NC-Pad1)") (class "Default")
      (node (ref "U2") (pin "1") (pinfunction "NC_1") (pintype "passive"))
    )
    (net (code "72") (name "unconnected-(U2-PA2_(AD2)-Pad49)") (class "Default")
      (node (ref "U2") (pin "49") (pinfunction "PA2_(AD2)_49") (pintype "bidirectional"))
    )
    (net (code "73") (name "unconnected-(U2-PA3_(AD3)-Pad48)") (class "Default")
      (node (ref "U2") (pin "48") (pinfunction "PA3_(AD3)_48") (pintype "bidirectional"))
    )
    (net (code "74") (name "unconnected-(U2-PA4_(AD4)-Pad47)") (class "Default")
      (node (ref "U2") (pin "47") (pinfunction "PA4_(AD4)_47") (pintype "bidirectional"))
    )
    (net (code "75") (name "unconnected-(U2-PA5_(AD5)-Pad46)") (class "Default")
      (node (ref "U2") (pin "46") (pinfunction "PA5_(AD5)_46") (pintype "bidirectional"))
    )
    (net (code "76") (name "unconnected-(U2-PA6_(AD6)-Pad45)") (class "Default")
      (node (ref "U2") (pin "45") (pinfunction "PA6_(AD6)_45") (pintype "bidirectional"))
    )
    (net (code "77") (name "unconnected-(U2-PA7_(AD7)-Pad44)") (class "Default")
      (node (ref "U2") (pin "44") (pinfunction "PA7_(AD7)_44") (pintype "bidirectional"))
    )
    (net (code "78") (name "unconnected-(U2-PC0_(A8)-Pad35)") (class "Default")
      (node (ref "U2") (pin "35") (pinfunction "PC0_(A8)_35") (pintype "bidirectional"))
    )
    (net (code "79") (name "unconnected-(U2-PC1_(A9)-Pad36)") (class "Default")
      (node (ref "U2") (pin "36") (pinfunction "PC1_(A9)_36") (pintype "bidirectional"))
    )
    (net (code "80") (name "unconnected-(U2-PC2_(A10)-Pad37)") (class "Default")
      (node (ref "U2") (pin "37") (pinfunction "PC2_(A10)_37") (pintype "bidirectional"))
    )
    (net (code "81") (name "unconnected-(U2-PC3_(A11)-Pad38)") (class "Default")
      (node (ref "U2") (pin "38") (pinfunction "PC3_(A11)_38") (pintype "bidirectional"))
    )
    (net (code "82") (name "unconnected-(U2-PC4_(A12)-Pad39)") (class "Default")
      (node (ref "U2") (pin "39") (pinfunction "PC4_(A12)_39") (pintype "bidirectional"))
    )
    (net (code "83") (name "unconnected-(U2-PC5_(A13)-Pad40)") (class "Default")
      (node (ref "U2") (pin "40") (pinfunction "PC5_(A13)_40") (pintype "bidirectional"))
    )
    (net (code "84") (name "unconnected-(U2-PC6_(A14)-Pad41)") (class "Default")
      (node (ref "U2") (pin "41") (pinfunction "PC6_(A14)_41") (pintype "bidirectional"))
    )
    (net (code "85") (name "unconnected-(U2-PC7_(A15_{slash}_CLKO)-Pad42)") (class "Default")
      (node (ref "U2") (pin "42") (pinfunction "PC7_(A15_/_CLKO)_42") (pintype "bidirectional"))
    )
    (net (code "86") (name "unconnected-(U2-PF1_(ADC1)-Pad60)") (class "Default")
      (node (ref "U2") (pin "60") (pinfunction "PF1_(ADC1)_60") (pintype "bidirectional"))
    )
    (net (code "87") (name "unconnected-(U2-PF2_(ADC2)-Pad59)") (class "Default")
      (node (ref "U2") (pin "59") (pinfunction "PF2_(ADC2)_59") (pintype "bidirectional"))
    )
    (net (code "88") (name "unconnected-(U2-PF3_(ADC3)-Pad58)") (class "Default")
      (node (ref "U2") (pin "58") (pinfunction "PF3_(ADC3)_58") (pintype "bidirectional"))
    )
    (net (code "89") (name "unconnected-(U2-PG0_(~{WR)}-Pad33)") (class "Default")
      (node (ref "U2") (pin "33") (pinfunction "PG0_(~{WR)}_33") (pintype "bidirectional"))
    )
    (net (code "90") (name "unconnected-(U2-PG1_(~{RD)}-Pad34)") (class "Default")
      (node (ref "U2") (pin "34") (pinfunction "PG1_(~{RD)}_34") (pintype "bidirectional"))
    )
    (net (code "91") (name "unconnected-(U2-PG2_(ALE)-Pad43)") (class "Default")
      (node (ref "U2") (pin "43") (pinfunction "PG2_(ALE)_43") (pintype "bidirectional"))
    )
    (net (code "92") (name "unconnected-(U7-DNC-Pad8)") (class "Default")
      (node (ref "U7") (pin "8") (pinfunction "DNC_8") (pintype "passive"))
    )
    (net (code "93") (name "unconnected-(U9-DNC-Pad8)") (class "Default")
      (node (ref "U9") (pin "8") (pinfunction "DNC_8") (pintype "passive"))
    )
  )
)
